# SCH_Controller.net
KiCad netlist of a schematic drawn in Altium Designer
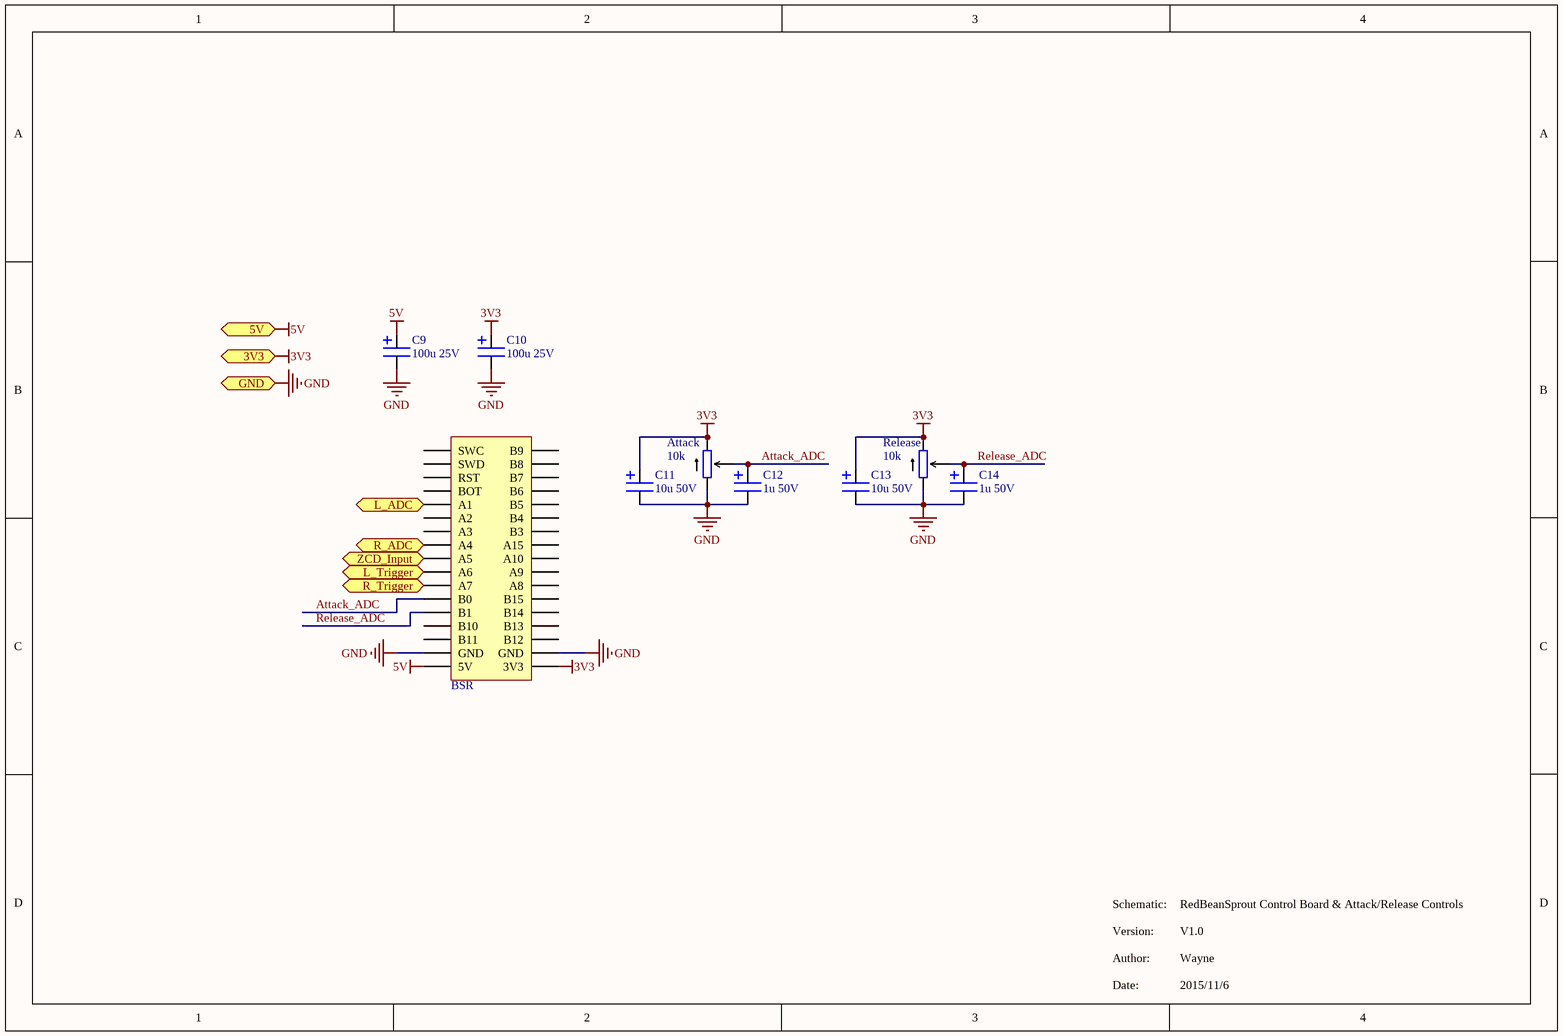
[diagram p0: SCH_Controller.SchDoc]

(export (version "E")
  (design (tool "Eeschema 10.0.6"))
  (components
    (comp (ref "Attack")
      (value "10k")
      (footprint "PCB_LIB:POT RK09K1130AAU")
      (description "ALPS POT RK09K1130AAU")
      (fields (field (name "Comment") "Single POT"))
      (libsource (lib "SCH_LIB") (part "ALPS POT RK09K1130AAU"))
    )
    (comp (ref "BSR")
      (value "BSR")
      (footprint "PCB_LIB:BSR")
      (description "Bean Sprout Red Socket")
      (libsource (lib "SCH_LIB") (part "BSR"))
    )
    (comp (ref "C9")
      (value "100u 25V")
      (footprint "PCB_LIB:CAP Axial 6.3mm")
      (description "Axial Cap")
      (fields (field (name "Comment") "Cap"))
      (libsource (lib "SCH_LIB") (part "Axial Cap"))
    )
    (comp (ref "C10")
      (value "100u 25V")
      (footprint "PCB_LIB:CAP Axial 6.3mm")
      (description "Axial Cap")
      (fields (field (name "Comment") "Cap"))
      (libsource (lib "SCH_LIB") (part "Axial Cap"))
    )
    (comp (ref "C11")
      (value "10u 50V")
      (footprint "PCB_LIB:CAP Axial 5mm")
      (description "Axial Cap")
      (fields (field (name "Comment") "Cap"))
      (libsource (lib "SCH_LIB") (part "Axial Cap"))
    )
    (comp (ref "C12")
      (value "1u 50V")
      (footprint "PCB_LIB:CAP Axial 5mm")
      (description "Axial Cap")
      (fields (field (name "Comment") "Cap"))
      (libsource (lib "SCH_LIB") (part "Axial Cap"))
    )
    (comp (ref "C13")
      (value "10u 50V")
      (footprint "PCB_LIB:CAP Axial 5mm")
      (description "Axial Cap")
      (fields (field (name "Comment") "Cap"))
      (libsource (lib "SCH_LIB") (part "Axial Cap"))
    )
    (comp (ref "C14")
      (value "1u 50V")
      (footprint "PCB_LIB:CAP Axial 5mm")
      (description "Axial Cap")
      (fields (field (name "Comment") "Cap"))
      (libsource (lib "SCH_LIB") (part "Axial Cap"))
    )
    (comp (ref "Release")
      (value "10k")
      (footprint "PCB_LIB:POT RK09K1130AAU")
      (description "ALPS POT RK09K1130AAU")
      (fields (field (name "Comment") "Single POT"))
      (libsource (lib "SCH_LIB") (part "ALPS POT RK09K1130AAU"))
    )
  )
  (nets
    (net (code "1") (name "/Attack_ADC") (class "Default")
      (node (ref "Attack") (pin "2") (pinfunction "2_2") (pintype "passive"))
      (node (ref "BSR") (pin "12") (pinfunction "B0_12") (pintype "passive"))
      (node (ref "C12") (pin "2") (pinfunction "2_2") (pintype "passive"))
    )
    (net (code "2") (name "/L_ADC") (class "Default")
      (node (ref "BSR") (pin "5") (pinfunction "A1_5") (pintype "passive"))
    )
    (net (code "3") (name "/L_Trigger") (class "Default")
      (node (ref "BSR") (pin "10") (pinfunction "A6_10") (pintype "passive"))
    )
    (net (code "4") (name "/R_ADC") (class "Default")
      (node (ref "BSR") (pin "8") (pinfunction "A4_8") (pintype "passive"))
    )
    (net (code "5") (name "/R_Trigger") (class "Default")
      (node (ref "BSR") (pin "11") (pinfunction "A7_11") (pintype "passive"))
    )
    (net (code "6") (name "/Release_ADC") (class "Default")
      (node (ref "BSR") (pin "13") (pinfunction "B1_13") (pintype "passive"))
      (node (ref "C14") (pin "2") (pinfunction "2_2") (pintype "passive"))
      (node (ref "Release") (pin "2") (pinfunction "2_2") (pintype "passive"))
    )
    (net (code "7") (name "/ZCD_Input") (class "Default")
      (node (ref "BSR") (pin "9") (pinfunction "A5_9") (pintype "passive"))
    )
    (net (code "8") (name "3V3") (class "Default")
      (node (ref "Attack") (pin "3") (pinfunction "3_3") (pintype "passive"))
      (node (ref "BSR") (pin "18") (pinfunction "3V3_18") (pintype "passive"))
      (node (ref "C10") (pin "2") (pinfunction "2_2") (pintype "passive"))
      (node (ref "C11") (pin "2") (pinfunction "2_2") (pintype "passive"))
      (node (ref "C13") (pin "2") (pinfunction "2_2") (pintype "passive"))
      (node (ref "Release") (pin "3") (pinfunction "3_3") (pintype "passive"))
    )
    (net (code "9") (name "5V") (class "Default")
      (node (ref "BSR") (pin "17") (pinfunction "5V_17") (pintype "passive"))
      (node (ref "C9") (pin "2") (pinfunction "2_2") (pintype "passive"))
    )
    (net (code "10") (name "GND") (class "Default")
      (node (ref "Attack") (pin "1") (pinfunction "1_1") (pintype "passive"))
      (node (ref "BSR") (pin "16") (pinfunction "GND_16") (pintype "passive"))
      (node (ref "BSR") (pin "19") (pinfunction "GND_19") (pintype "passive"))
      (node (ref "C10") (pin "1") (pinfunction "1_1") (pintype "passive"))
      (node (ref "C11") (pin "1") (pinfunction "1_1") (pintype "passive"))
      (node (ref "C12") (pin "1") (pinfunction "1_1") (pintype "passive"))
      (node (ref "C13") (pin "1") (pinfunction "1_1") (pintype "passive"))
      (node (ref "C14") (pin "1") (pinfunction "1_1") (pintype "passive"))
      (node (ref "C9") (pin "1") (pinfunction "1_1") (pintype "passive"))
      (node (ref "Release") (pin "1") (pinfunction "1_1") (pintype "passive"))
    )
    (net (code "11") (name "unconnected-(BSR-A2-Pad6)") (class "Default")
      (node (ref "BSR") (pin "6") (pinfunction "A2_6") (pintype "passive"))
    )
    (net (code "12") (name "unconnected-(BSR-A3-Pad7)") (class "Default")
      (node (ref "BSR") (pin "7") (pinfunction "A3_7") (pintype "passive"))
    )
    (net (code "13") (name "unconnected-(BSR-A8-Pad24)") (class "Default")
      (node (ref "BSR") (pin "24") (pinfunction "A8_24") (pintype "passive"))
    )
    (net (code "14") (name "unconnected-(BSR-A9-Pad25)") (class "Default")
      (node (ref "BSR") (pin "25") (pinfunction "A9_25") (pintype "passive"))
    )
    (net (code "15") (name "unconnected-(BSR-A10-Pad26)") (class "Default")
      (node (ref "BSR") (pin "26") (pinfunction "A10_26") (pintype "passive"))
    )
    (net (code "16") (name "unconnected-(BSR-A15-Pad27)") (class "Default")
      (node (ref "BSR") (pin "27") (pinfunction "A15_27") (pintype "passive"))
    )
    (net (code "17") (name "unconnected-(BSR-B3-Pad28)") (class "Default")
      (node (ref "BSR") (pin "28") (pinfunction "B3_28") (pintype "passive"))
    )
    (net (code "18") (name "unconnected-(BSR-B4-Pad29)") (class "Default")
      (node (ref "BSR") (pin "29") (pinfunction "B4_29") (pintype "passive"))
    )
    (net (code "19") (name "unconnected-(BSR-B5-Pad30)") (class "Default")
      (node (ref "BSR") (pin "30") (pinfunction "B5_30") (pintype "passive"))
    )
    (net (code "20") (name "unconnected-(BSR-B6-Pad31)") (class "Default")
      (node (ref "BSR") (pin "31") (pinfunction "B6_31") (pintype "passive"))
    )
    (net (code "21") (name "unconnected-(BSR-B7-Pad32)") (class "Default")
      (node (ref "BSR") (pin "32") (pinfunction "B7_32") (pintype "passive"))
    )
    (net (code "22") (name "unconnected-(BSR-B8-Pad33)") (class "Default")
      (node (ref "BSR") (pin "33") (pinfunction "B8_33") (pintype "passive"))
    )
    (net (code "23") (name "unconnected-(BSR-B9-Pad34)") (class "Default")
      (node (ref "BSR") (pin "34") (pinfunction "B9_34") (pintype "passive"))
    )
    (net (code "24") (name "unconnected-(BSR-B10-Pad14)") (class "Default")
      (node (ref "BSR") (pin "14") (pinfunction "B10_14") (pintype "passive"))
    )
    (net (code "25") (name "unconnected-(BSR-B11-Pad15)") (class "Default")
      (node (ref "BSR") (pin "15") (pinfunction "B11_15") (pintype "passive"))
    )
    (net (code "26") (name "unconnected-(BSR-B12-Pad20)") (class "Default")
      (node (ref "BSR") (pin "20") (pinfunction "B12_20") (pintype "passive"))
    )
    (net (code "27") (name "unconnected-(BSR-B13-Pad21)") (class "Default")
      (node (ref "BSR") (pin "21") (pinfunction "B13_21") (pintype "passive"))
    )
    (net (code "28") (name "unconnected-(BSR-B14-Pad22)") (class "Default")
      (node (ref "BSR") (pin "22") (pinfunction "B14_22") (pintype "passive"))
    )
    (net (code "29") (name "unconnected-(BSR-B15-Pad23)") (class "Default")
      (node (ref "BSR") (pin "23") (pinfunction "B15_23") (pintype "passive"))
    )
    (net (code "30") (name "unconnected-(BSR-BOT-Pad4)") (class "Default")
      (node (ref "BSR") (pin "4") (pinfunction "BOT_4") (pintype "passive"))
    )
    (net (code "31") (name "unconnected-(BSR-RST-Pad3)") (class "Default")
      (node (ref "BSR") (pin "3") (pinfunction "RST_3") (pintype "passive"))
    )
    (net (code "32") (name "unconnected-(BSR-SWC-Pad1)") (class "Default")
      (node (ref "BSR") (pin "1") (pinfunction "SWC_1") (pintype "passive"))
    )
    (net (code "33") (name "unconnected-(BSR-SWD-Pad2)") (class "Default")
      (node (ref "BSR") (pin "2") (pinfunction "SWD_2") (pintype "passive"))
    )
  )
)
